# 12.net
KiCad netlist of a schematic drawn in EAGLE
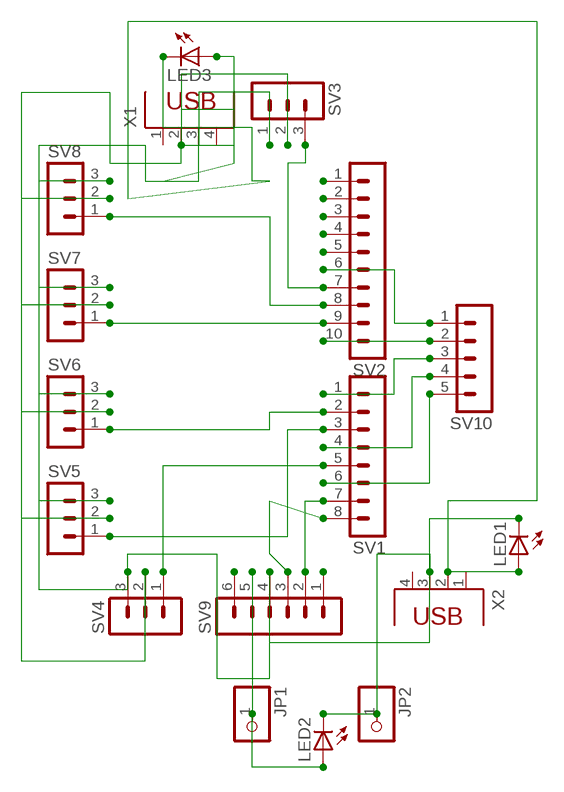
[diagram p0: schematic, sheet 1]

(export (version "E")
  (design (tool "Eeschema 10.0.6"))
  (components
    (comp (ref "JP1")
      (value "PINHD-1X1")
      (footprint "eagle-import:1X01")
      (libsource (lib "eagle-import") (part "PINHD-1X1"))
    )
    (comp (ref "JP2")
      (value "PINHD-1X1")
      (footprint "eagle-import:1X01")
      (libsource (lib "eagle-import") (part "PINHD-1X1"))
    )
    (comp (ref "LED1")
      (value "LEDLD260")
      (footprint "eagle-import:LD260")
      (libsource (lib "eagle-import") (part "LEDLD260"))
    )
    (comp (ref "LED2")
      (value "LEDLD260")
      (footprint "eagle-import:LD260")
      (libsource (lib "eagle-import") (part "LEDLD260"))
    )
    (comp (ref "LED3")
      (value "LEDLD260")
      (footprint "eagle-import:LD260")
      (libsource (lib "eagle-import") (part "LEDLD260"))
    )
    (comp (ref "SV1")
      (value "MA08-1")
      (footprint "eagle-import:MA08-1")
      (libsource (lib "eagle-import") (part "MA08-1"))
    )
    (comp (ref "SV2")
      (value "MA10-1")
      (footprint "eagle-import:MA10-1")
      (libsource (lib "eagle-import") (part "MA10-1"))
    )
    (comp (ref "SV3")
      (value "MA03-1")
      (footprint "eagle-import:MA03-1")
      (libsource (lib "eagle-import") (part "MA03-1"))
    )
    (comp (ref "SV4")
      (value "MA03-1")
      (footprint "eagle-import:MA03-1")
      (libsource (lib "eagle-import") (part "MA03-1"))
    )
    (comp (ref "SV5")
      (value "MA03-1")
      (footprint "eagle-import:MA03-1")
      (libsource (lib "eagle-import") (part "MA03-1"))
    )
    (comp (ref "SV6")
      (value "MA03-1")
      (footprint "eagle-import:MA03-1")
      (libsource (lib "eagle-import") (part "MA03-1"))
    )
    (comp (ref "SV7")
      (value "MA03-1")
      (footprint "eagle-import:MA03-1")
      (libsource (lib "eagle-import") (part "MA03-1"))
    )
    (comp (ref "SV8")
      (value "MA03-1")
      (footprint "eagle-import:MA03-1")
      (libsource (lib "eagle-import") (part "MA03-1"))
    )
    (comp (ref "SV9")
      (value "MA06-1")
      (footprint "eagle-import:MA06-1")
      (libsource (lib "eagle-import") (part "MA06-1"))
    )
    (comp (ref "SV10")
      (value "MA05-1")
      (footprint "eagle-import:MA05-1")
      (libsource (lib "eagle-import") (part "MA05-1"))
    )
    (comp (ref "X1")
      (value "PN61729")
      (footprint "eagle-import:PN61729")
      (libsource (lib "eagle-import") (part "PN61729"))
    )
    (comp (ref "X2")
      (value "PN61729")
      (footprint "eagle-import:PN61729")
      (libsource (lib "eagle-import") (part "PN61729"))
    )
  )
  (nets
    (net (code "1") (name "Net-(JP1-Pad1)") (class "Default")
      (node (ref "JP1") (pin "1") (pinfunction "1_1") (pintype "passive"))
      (node (ref "LED2") (pin "A") (pinfunction "A_A") (pintype "passive"))
      (node (ref "SV9") (pin "5") (pinfunction "5_5") (pintype "passive"))
    )
    (net (code "2") (name "Net-(LED1-C)") (class "Default")
      (node (ref "JP2") (pin "1") (pinfunction "1_1") (pintype "passive"))
      (node (ref "LED1") (pin "K") (pinfunction "C_K") (pintype "passive"))
      (node (ref "LED2") (pin "K") (pinfunction "C_K") (pintype "passive"))
      (node (ref "LED3") (pin "K") (pinfunction "C_K") (pintype "passive"))
      (node (ref "SV3") (pin "1") (pinfunction "1_1") (pintype "passive"))
      (node (ref "SV4") (pin "3") (pinfunction "3_3") (pintype "passive"))
      (node (ref "SV5") (pin "3") (pinfunction "3_3") (pintype "passive"))
      (node (ref "SV6") (pin "3") (pinfunction "3_3") (pintype "passive"))
      (node (ref "SV7") (pin "3") (pinfunction "3_3") (pintype "passive"))
      (node (ref "SV8") (pin "3") (pinfunction "3_3") (pintype "passive"))
      (node (ref "SV9") (pin "4") (pinfunction "4_4") (pintype "passive"))
      (node (ref "X1") (pin "3") (pinfunction "3_3") (pintype "passive"))
      (node (ref "X2") (pin "3") (pinfunction "3_3") (pintype "passive"))
    )
    (net (code "3") (name "Net-(LED1-PadA)") (class "Default")
      (node (ref "LED1") (pin "A") (pinfunction "A_A") (pintype "passive"))
      (node (ref "LED3") (pin "A") (pinfunction "A_A") (pintype "passive"))
      (node (ref "SV3") (pin "2") (pinfunction "2_2") (pintype "passive"))
      (node (ref "SV4") (pin "2") (pinfunction "2_2") (pintype "passive"))
      (node (ref "SV5") (pin "2") (pinfunction "2_2") (pintype "passive"))
      (node (ref "SV6") (pin "2") (pinfunction "2_2") (pintype "passive"))
      (node (ref "SV7") (pin "2") (pinfunction "2_2") (pintype "passive"))
      (node (ref "SV8") (pin "2") (pinfunction "2_2") (pintype "passive"))
      (node (ref "X1") (pin "2") (pinfunction "2_2") (pintype "passive"))
      (node (ref "X2") (pin "2") (pinfunction "2_2") (pintype "passive"))
    )
    (net (code "4") (name "Net-(SV1-Pad1)") (class "Default")
      (node (ref "SV1") (pin "1") (pinfunction "1_1") (pintype "passive"))
      (node (ref "SV10") (pin "3") (pinfunction "3_3") (pintype "passive"))
    )
    (net (code "5") (name "Net-(SV1-Pad2)") (class "Default")
      (node (ref "SV1") (pin "2") (pinfunction "2_2") (pintype "passive"))
      (node (ref "SV6") (pin "1") (pinfunction "1_1") (pintype "passive"))
    )
    (net (code "6") (name "Net-(SV1-Pad3)") (class "Default")
      (node (ref "SV1") (pin "3") (pinfunction "3_3") (pintype "passive"))
      (node (ref "SV5") (pin "1") (pinfunction "1_1") (pintype "passive"))
    )
    (net (code "7") (name "Net-(SV1-Pad4)") (class "Default")
      (node (ref "SV1") (pin "4") (pinfunction "4_4") (pintype "passive"))
      (node (ref "SV10") (pin "4") (pinfunction "4_4") (pintype "passive"))
    )
    (net (code "8") (name "Net-(SV1-Pad5)") (class "Default")
      (node (ref "SV1") (pin "5") (pinfunction "5_5") (pintype "passive"))
      (node (ref "SV4") (pin "1") (pinfunction "1_1") (pintype "passive"))
    )
    (net (code "9") (name "Net-(SV1-Pad6)") (class "Default")
      (node (ref "SV1") (pin "6") (pinfunction "6_6") (pintype "passive"))
      (node (ref "SV10") (pin "5") (pinfunction "5_5") (pintype "passive"))
    )
    (net (code "10") (name "Net-(SV1-Pad7)") (class "Default")
      (node (ref "SV1") (pin "7") (pinfunction "7_7") (pintype "passive"))
      (node (ref "SV9") (pin "2") (pinfunction "2_2") (pintype "passive"))
    )
    (net (code "11") (name "Net-(SV1-Pad8)") (class "Default")
      (node (ref "SV1") (pin "8") (pinfunction "8_8") (pintype "passive"))
      (node (ref "SV9") (pin "3") (pinfunction "3_3") (pintype "passive"))
    )
    (net (code "12") (name "Net-(SV2-Pad7)") (class "Default")
      (node (ref "SV2") (pin "7") (pinfunction "7_7") (pintype "passive"))
      (node (ref "SV3") (pin "3") (pinfunction "3_3") (pintype "passive"))
    )
    (net (code "13") (name "Net-(SV2-Pad8)") (class "Default")
      (node (ref "SV2") (pin "8") (pinfunction "8_8") (pintype "passive"))
      (node (ref "SV8") (pin "1") (pinfunction "1_1") (pintype "passive"))
    )
    (net (code "14") (name "Net-(SV2-Pad9)") (class "Default")
      (node (ref "SV2") (pin "9") (pinfunction "9_9") (pintype "passive"))
      (node (ref "SV7") (pin "1") (pinfunction "1_1") (pintype "passive"))
    )
    (net (code "15") (name "Net-(SV10-Pad1)") (class "Default")
      (node (ref "SV10") (pin "1") (pinfunction "1_1") (pintype "passive"))
      (node (ref "SV2") (pin "6") (pinfunction "6_6") (pintype "passive"))
    )
    (net (code "16") (name "Net-(SV10-Pad2)") (class "Default")
      (node (ref "SV10") (pin "2") (pinfunction "2_2") (pintype "passive"))
      (node (ref "SV2") (pin "10") (pinfunction "10_10") (pintype "passive"))
    )
    (net (code "17") (name "unconnected-(SV2-Pad1)") (class "Default")
      (node (ref "SV2") (pin "1") (pinfunction "1_1") (pintype "passive"))
    )
    (net (code "18") (name "unconnected-(SV2-Pad2)") (class "Default")
      (node (ref "SV2") (pin "2") (pinfunction "2_2") (pintype "passive"))
    )
    (net (code "19") (name "unconnected-(SV2-Pad3)") (class "Default")
      (node (ref "SV2") (pin "3") (pinfunction "3_3") (pintype "passive"))
    )
    (net (code "20") (name "unconnected-(SV2-Pad4)") (class "Default")
      (node (ref "SV2") (pin "4") (pinfunction "4_4") (pintype "passive"))
    )
    (net (code "21") (name "unconnected-(SV2-Pad5)") (class "Default")
      (node (ref "SV2") (pin "5") (pinfunction "5_5") (pintype "passive"))
    )
    (net (code "22") (name "unconnected-(SV9-Pad1)") (class "Default")
      (node (ref "SV9") (pin "1") (pinfunction "1_1") (pintype "passive"))
    )
    (net (code "23") (name "unconnected-(SV9-Pad6)") (class "Default")
      (node (ref "SV9") (pin "6") (pinfunction "6_6") (pintype "passive"))
    )
    (net (code "24") (name "unconnected-(X1-Pad1)") (class "Default")
      (node (ref "X1") (pin "1") (pinfunction "1_1") (pintype "passive"))
    )
    (net (code "25") (name "unconnected-(X1-Pad4)") (class "Default")
      (node (ref "X1") (pin "4") (pinfunction "4_4") (pintype "passive"))
    )
    (net (code "26") (name "unconnected-(X2-Pad1)") (class "Default")
      (node (ref "X2") (pin "1") (pinfunction "1_1") (pintype "passive"))
    )
    (net (code "27") (name "unconnected-(X2-Pad4)") (class "Default")
      (node (ref "X2") (pin "4") (pinfunction "4_4") (pintype "passive"))
    )
  )
)
